# PropVGA.net
KiCad netlist of a schematic drawn in EAGLE
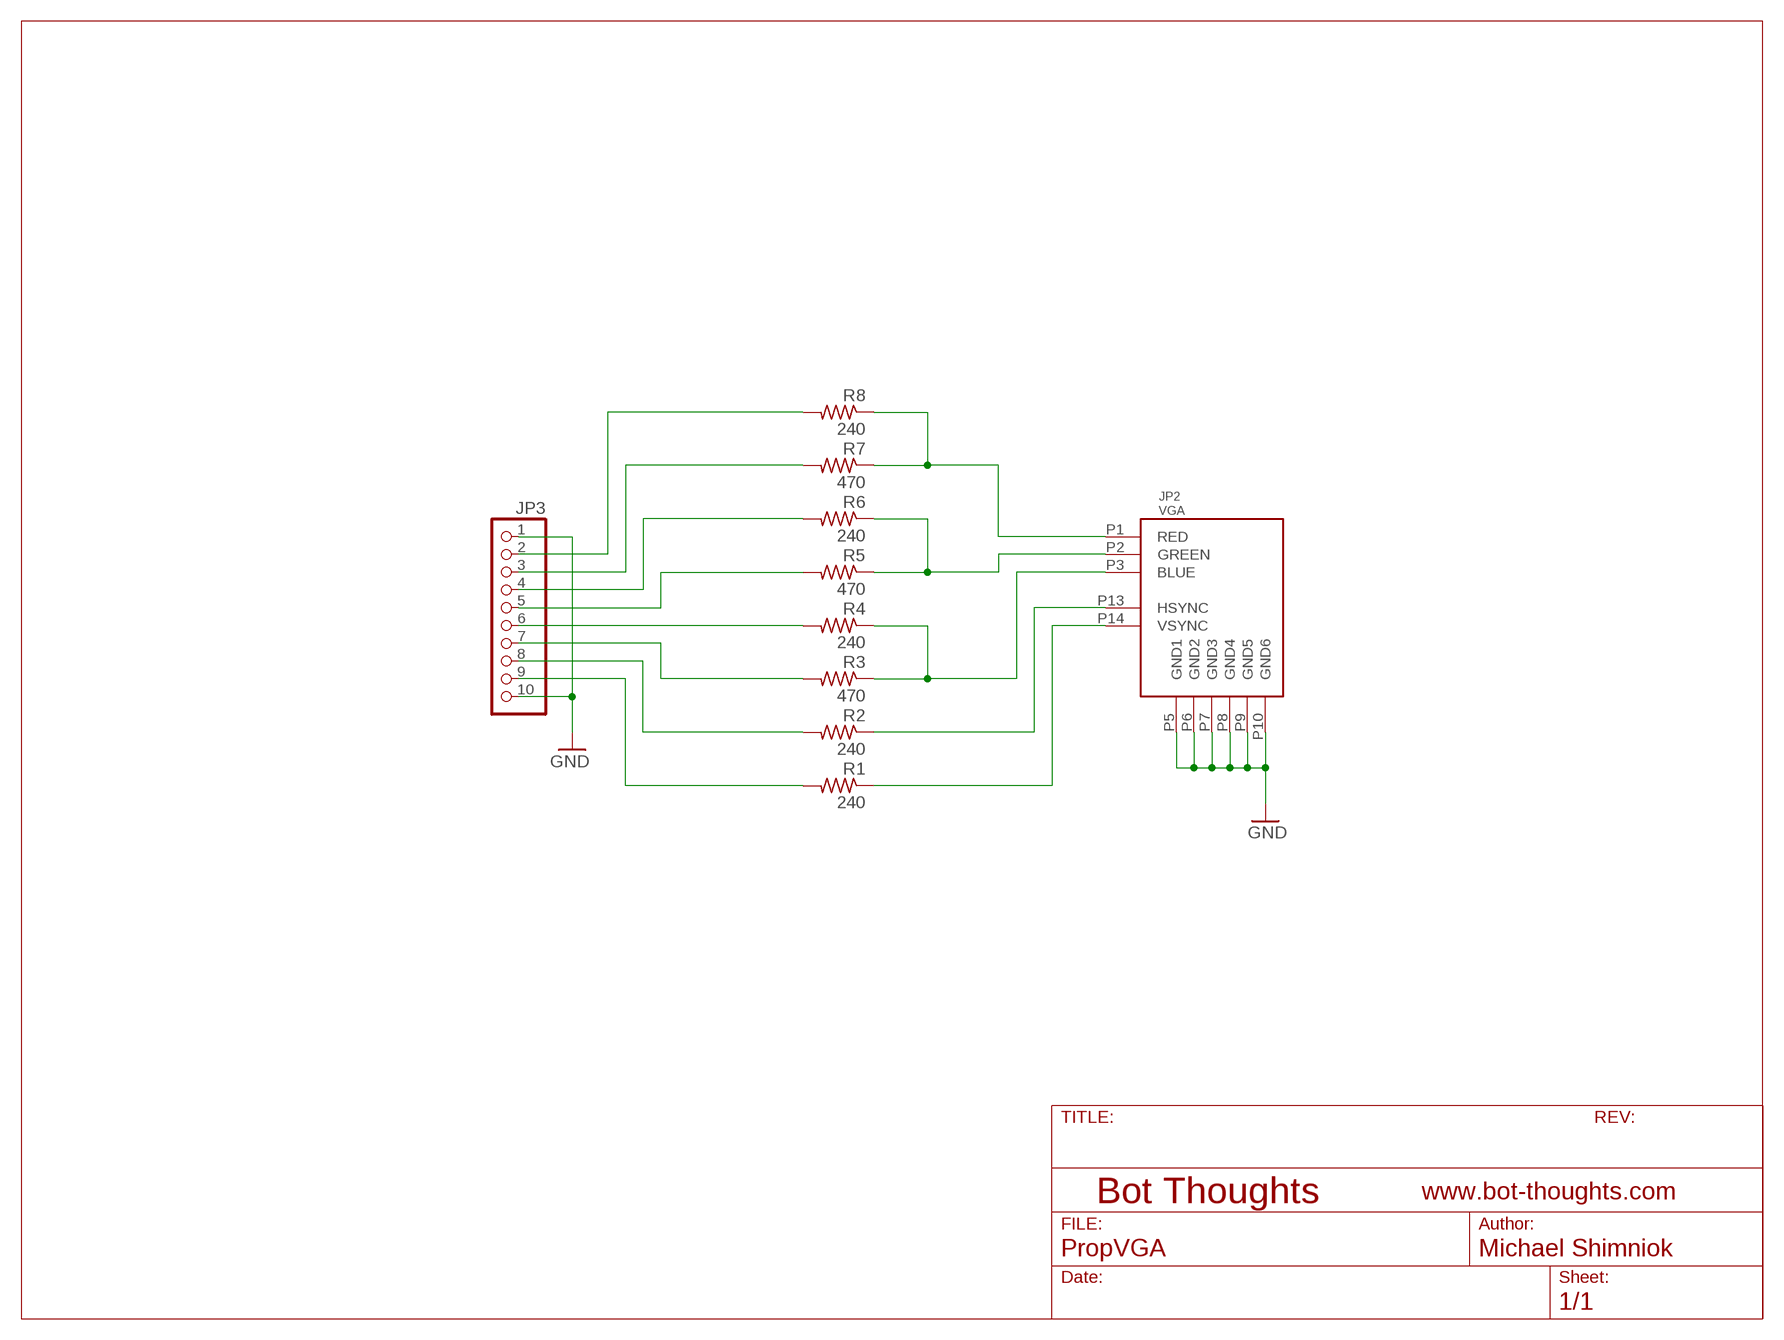
[diagram p0: schematic, sheet 1]

(export (version "E")
  (design (tool "Eeschema 10.0.6"))
  (components
    (comp (ref "JP2")
      (value "VGA")
      (footprint "eagle-import:FCI_DSUB_HD_15_RA")
      (libsource (lib "eagle-import") (part "VGA"))
    )
    (comp (ref "JP3")
      (value "PINHD-1X10_2.54-S")
      (footprint "eagle-import:1X10-S")
      (libsource (lib "eagle-import") (part "PINHD-1X10_2.54-S"))
    )
    (comp (ref "R1")
      (value "240")
      (footprint "eagle-import:0204_5")
      (libsource (lib "eagle-import") (part "R-US_0204/5"))
    )
    (comp (ref "R2")
      (value "240")
      (footprint "eagle-import:0204_5")
      (libsource (lib "eagle-import") (part "R-US_0204/5"))
    )
    (comp (ref "R3")
      (value "470")
      (footprint "eagle-import:0204_5")
      (libsource (lib "eagle-import") (part "R-US_0204/5"))
    )
    (comp (ref "R4")
      (value "240")
      (footprint "eagle-import:0204_5")
      (libsource (lib "eagle-import") (part "R-US_0204/5"))
    )
    (comp (ref "R5")
      (value "470")
      (footprint "eagle-import:0204_5")
      (libsource (lib "eagle-import") (part "R-US_0204/5"))
    )
    (comp (ref "R6")
      (value "240")
      (footprint "eagle-import:0204_5")
      (libsource (lib "eagle-import") (part "R-US_0204/5"))
    )
    (comp (ref "R7")
      (value "470")
      (footprint "eagle-import:0204_5")
      (libsource (lib "eagle-import") (part "R-US_0204/5"))
    )
    (comp (ref "R8")
      (value "240")
      (footprint "eagle-import:0204_5")
      (libsource (lib "eagle-import") (part "R-US_0204/5"))
    )
  )
  (nets
    (net (code "1") (name "GND") (class "Default")
      (node (ref "JP2") (pin "P10") (pinfunction "GND6_P10") (pintype "bidirectional"))
      (node (ref "JP2") (pin "P5") (pinfunction "GND1_P5") (pintype "bidirectional"))
      (node (ref "JP2") (pin "P6") (pinfunction "GND2_P6") (pintype "bidirectional"))
      (node (ref "JP2") (pin "P7") (pinfunction "GND3_P7") (pintype "bidirectional"))
      (node (ref "JP2") (pin "P8") (pinfunction "GND4_P8") (pintype "bidirectional"))
      (node (ref "JP2") (pin "P9") (pinfunction "GND5_P9") (pintype "bidirectional"))
      (node (ref "JP3") (pin "1") (pinfunction "1_1") (pintype "passive"))
      (node (ref "JP3") (pin "10") (pinfunction "10_10") (pintype "passive"))
    )
    (net (code "2") (name "Net-(JP2-BLUE)") (class "Default")
      (node (ref "JP2") (pin "P3") (pinfunction "BLUE_P3") (pintype "bidirectional"))
      (node (ref "R3") (pin "1") (pinfunction "1_1") (pintype "passive"))
      (node (ref "R4") (pin "1") (pinfunction "1_1") (pintype "passive"))
    )
    (net (code "3") (name "Net-(JP2-GREEN)") (class "Default")
      (node (ref "JP2") (pin "P2") (pinfunction "GREEN_P2") (pintype "bidirectional"))
      (node (ref "R5") (pin "1") (pinfunction "1_1") (pintype "passive"))
      (node (ref "R6") (pin "1") (pinfunction "1_1") (pintype "passive"))
    )
    (net (code "4") (name "Net-(JP2-HSYNC)") (class "Default")
      (node (ref "JP2") (pin "P13") (pinfunction "HSYNC_P13") (pintype "bidirectional"))
      (node (ref "R2") (pin "1") (pinfunction "1_1") (pintype "passive"))
    )
    (net (code "5") (name "Net-(JP2-RED)") (class "Default")
      (node (ref "JP2") (pin "P1") (pinfunction "RED_P1") (pintype "bidirectional"))
      (node (ref "R7") (pin "1") (pinfunction "1_1") (pintype "passive"))
      (node (ref "R8") (pin "1") (pinfunction "1_1") (pintype "passive"))
    )
    (net (code "6") (name "Net-(JP2-VSYNC)") (class "Default")
      (node (ref "JP2") (pin "P14") (pinfunction "VSYNC_P14") (pintype "bidirectional"))
      (node (ref "R1") (pin "1") (pinfunction "1_1") (pintype "passive"))
    )
    (net (code "7") (name "Net-(JP3-Pad2)") (class "Default")
      (node (ref "JP3") (pin "2") (pinfunction "2_2") (pintype "passive"))
      (node (ref "R8") (pin "2") (pinfunction "2_2") (pintype "passive"))
    )
    (net (code "8") (name "Net-(JP3-Pad3)") (class "Default")
      (node (ref "JP3") (pin "3") (pinfunction "3_3") (pintype "passive"))
      (node (ref "R7") (pin "2") (pinfunction "2_2") (pintype "passive"))
    )
    (net (code "9") (name "Net-(JP3-Pad4)") (class "Default")
      (node (ref "JP3") (pin "4") (pinfunction "4_4") (pintype "passive"))
      (node (ref "R6") (pin "2") (pinfunction "2_2") (pintype "passive"))
    )
    (net (code "10") (name "Net-(JP3-Pad5)") (class "Default")
      (node (ref "JP3") (pin "5") (pinfunction "5_5") (pintype "passive"))
      (node (ref "R5") (pin "2") (pinfunction "2_2") (pintype "passive"))
    )
    (net (code "11") (name "Net-(JP3-Pad6)") (class "Default")
      (node (ref "JP3") (pin "6") (pinfunction "6_6") (pintype "passive"))
      (node (ref "R4") (pin "2") (pinfunction "2_2") (pintype "passive"))
    )
    (net (code "12") (name "Net-(JP3-Pad7)") (class "Default")
      (node (ref "JP3") (pin "7") (pinfunction "7_7") (pintype "passive"))
      (node (ref "R3") (pin "2") (pinfunction "2_2") (pintype "passive"))
    )
    (net (code "13") (name "Net-(JP3-Pad8)") (class "Default")
      (node (ref "JP3") (pin "8") (pinfunction "8_8") (pintype "passive"))
      (node (ref "R2") (pin "2") (pinfunction "2_2") (pintype "passive"))
    )
    (net (code "14") (name "Net-(JP3-Pad9)") (class "Default")
      (node (ref "JP3") (pin "9") (pinfunction "9_9") (pintype "passive"))
      (node (ref "R1") (pin "2") (pinfunction "2_2") (pintype "passive"))
    )
  )
)
